# 13-EXTENSION.net
KiCad netlist of a schematic drawn in Altium Designer
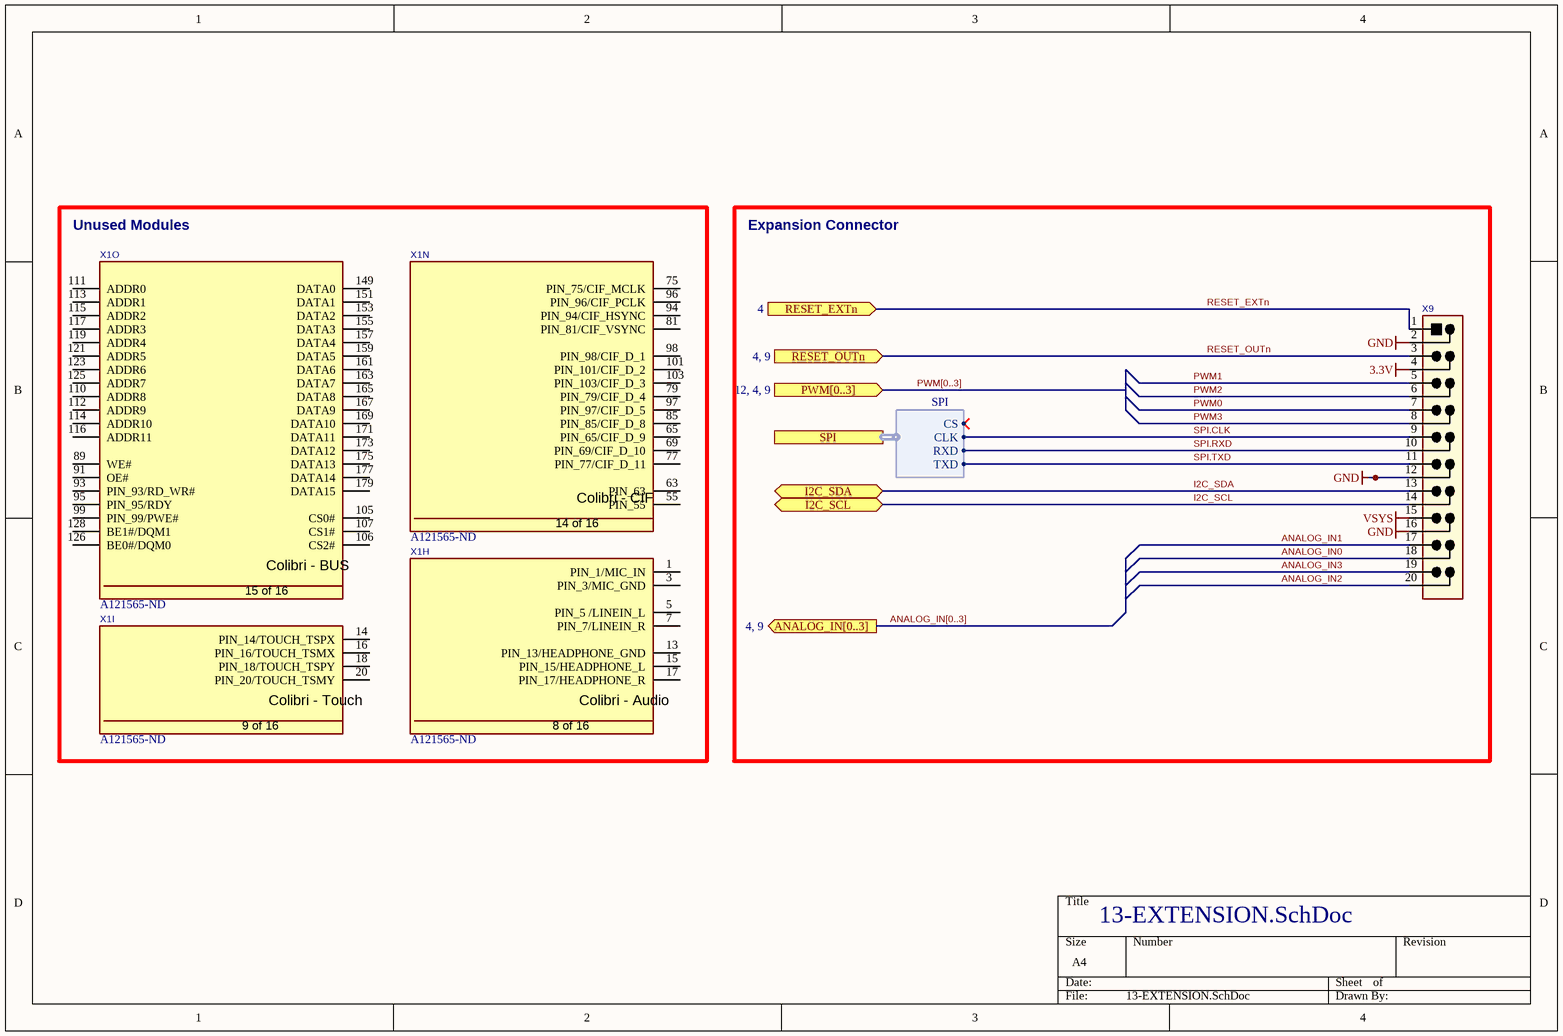
[diagram p0: 13-EXTENSION.SchDoc]

(export (version "E")
  (design (tool "Eeschema 10.0.6"))
  (components
    (comp (ref "X1")
      (value "1473005-1")
      (footprint "T_Tyco_1473005-1")
      (description "SODIMM Connector")
      (fields (field (name "SUPPLIER PART NUMBER 1") "A121565-ND"))
      (libsource (lib "Connectors") (part "CON-Tyco-1473005-1-200-0.6mm"))
    )
    (comp (ref "X9")
      (value "PH2-20-UA")
      (footprint "T_JVE_21B22564-40S10B-01G")
      (description "Connector Header Through Hole 20 position 0.100\" (2.54mm)")
      (fields (field (name "MFG") "FCI"))
      (libsource (lib "AI Gateway - Carrier") (part "CON-Adam-PH2-20-UA-2X10-2.54mm"))
    )
  )
  (nets
    (net (code "2") (name "/ANALOG_IN0") (class "Default")
      (node (ref "X9") (pin "18") (pinfunction "18_18") (pintype "passive"))
    )
    (net (code "3") (name "/ANALOG_IN1") (class "Default")
      (node (ref "X9") (pin "17") (pinfunction "17_17") (pintype "passive"))
    )
    (net (code "4") (name "/ANALOG_IN2") (class "Default")
      (node (ref "X9") (pin "20") (pinfunction "20_20") (pintype "passive"))
    )
    (net (code "5") (name "/ANALOG_IN3") (class "Default")
      (node (ref "X9") (pin "19") (pinfunction "19_19") (pintype "passive"))
    )
    (net (code "7") (name "/I2C_SCL") (class "Default")
      (node (ref "X9") (pin "14") (pinfunction "14_14") (pintype "passive"))
    )
    (net (code "8") (name "/I2C_SDA") (class "Default")
      (node (ref "X9") (pin "13") (pinfunction "13_13") (pintype "passive"))
    )
    (net (code "9") (name "/PWM0") (class "Default")
      (node (ref "X9") (pin "7") (pinfunction "7_7") (pintype "passive"))
    )
    (net (code "10") (name "/PWM1") (class "Default")
      (node (ref "X9") (pin "5") (pinfunction "5_5") (pintype "passive"))
    )
    (net (code "11") (name "/PWM2") (class "Default")
      (node (ref "X9") (pin "6") (pinfunction "6_6") (pintype "passive"))
    )
    (net (code "12") (name "/PWM3") (class "Default")
      (node (ref "X9") (pin "8") (pinfunction "8_8") (pintype "passive"))
    )
    (net (code "14") (name "/RESET_EXTn") (class "Default")
      (node (ref "X9") (pin "1") (pinfunction "1_1") (pintype "passive"))
    )
    (net (code "15") (name "/RESET_OUTn") (class "Default")
      (node (ref "X9") (pin "3") (pinfunction "3_3") (pintype "passive"))
    )
    (net (code "16") (name "/SPI.CLK") (class "Default")
      (node (ref "X9") (pin "9") (pinfunction "9_9") (pintype "passive"))
    )
    (net (code "17") (name "/SPI.RXD") (class "Default")
      (node (ref "X9") (pin "10") (pinfunction "10_10") (pintype "passive"))
    )
    (net (code "18") (name "/SPI.TXD") (class "Default")
      (node (ref "X9") (pin "11") (pinfunction "11_11") (pintype "passive"))
    )
    (net (code "20") (name "3.3V") (class "Default")
      (node (ref "X9") (pin "4") (pinfunction "4_4") (pintype "passive"))
    )
    (net (code "21") (name "GND") (class "Default")
      (node (ref "X9") (pin "12") (pinfunction "12_12") (pintype "passive"))
      (node (ref "X9") (pin "16") (pinfunction "16_16") (pintype "passive"))
      (node (ref "X9") (pin "2") (pinfunction "2_2") (pintype "passive"))
    )
    (net (code "22") (name "VSYS") (class "Default")
      (node (ref "X9") (pin "15") (pinfunction "15_15") (pintype "passive"))
    )
    (net (code "23") (name "unconnected-(X1H-PIN_1{slash}MIC_IN-Pad1)") (class "Default")
      (node (ref "X1") (pin "1") (pinfunction "PIN_1/MIC_IN_1") (pintype "passive"))
    )
    (net (code "24") (name "unconnected-(X1H-PIN_3{slash}MIC_GND-Pad3)") (class "Default")
      (node (ref "X1") (pin "3") (pinfunction "PIN_3/MIC_GND_3") (pintype "passive"))
    )
    (net (code "25") (name "unconnected-(X1H-PIN_5_{slash}LINEIN_L-Pad5)") (class "Default")
      (node (ref "X1") (pin "5") (pinfunction "PIN_5_/LINEIN_L_5") (pintype "passive"))
    )
    (net (code "26") (name "unconnected-(X1H-PIN_7{slash}LINEIN_R-Pad7)") (class "Default")
      (node (ref "X1") (pin "7") (pinfunction "PIN_7/LINEIN_R_7") (pintype "passive"))
    )
    (net (code "27") (name "unconnected-(X1H-PIN_13{slash}HEADPHONE_GND-Pad13)") (class "Default")
      (node (ref "X1") (pin "13") (pinfunction "PIN_13/HEADPHONE_GND_13") (pintype "passive"))
    )
    (net (code "28") (name "unconnected-(X1H-PIN_15{slash}HEADPHONE_L-Pad15)") (class "Default")
      (node (ref "X1") (pin "15") (pinfunction "PIN_15/HEADPHONE_L_15") (pintype "passive"))
    )
    (net (code "29") (name "unconnected-(X1H-PIN_17{slash}HEADPHONE_R-Pad17)") (class "Default")
      (node (ref "X1") (pin "17") (pinfunction "PIN_17/HEADPHONE_R_17") (pintype "passive"))
    )
    (net (code "30") (name "unconnected-(X1I-PIN_14{slash}TOUCH_TSPX-Pad14)") (class "Default")
      (node (ref "X1") (pin "14") (pinfunction "PIN_14/TOUCH_TSPX_14") (pintype "passive"))
    )
    (net (code "31") (name "unconnected-(X1I-PIN_16{slash}TOUCH_TSMX-Pad16)") (class "Default")
      (node (ref "X1") (pin "16") (pinfunction "PIN_16/TOUCH_TSMX_16") (pintype "passive"))
    )
    (net (code "32") (name "unconnected-(X1I-PIN_18{slash}TOUCH_TSPY-Pad18)") (class "Default")
      (node (ref "X1") (pin "18") (pinfunction "PIN_18/TOUCH_TSPY_18") (pintype "passive"))
    )
    (net (code "33") (name "unconnected-(X1I-PIN_20{slash}TOUCH_TSMY-Pad20)") (class "Default")
      (node (ref "X1") (pin "20") (pinfunction "PIN_20/TOUCH_TSMY_20") (pintype "passive"))
    )
    (net (code "34") (name "unconnected-(X1N-PIN_55-Pad55)") (class "Default")
      (node (ref "X1") (pin "55") (pinfunction "PIN_55_55") (pintype "passive"))
    )
    (net (code "35") (name "unconnected-(X1N-PIN_63-Pad63)") (class "Default")
      (node (ref "X1") (pin "63") (pinfunction "PIN_63_63") (pintype "passive"))
    )
    (net (code "36") (name "unconnected-(X1N-PIN_65{slash}CIF_D_9-Pad65)") (class "Default")
      (node (ref "X1") (pin "65") (pinfunction "PIN_65/CIF_D_9_65") (pintype "passive"))
    )
    (net (code "37") (name "unconnected-(X1N-PIN_69{slash}CIF_D_10-Pad69)") (class "Default")
      (node (ref "X1") (pin "69") (pinfunction "PIN_69/CIF_D_10_69") (pintype "passive"))
    )
    (net (code "38") (name "unconnected-(X1N-PIN_75{slash}CIF_MCLK-Pad75)") (class "Default")
      (node (ref "X1") (pin "75") (pinfunction "PIN_75/CIF_MCLK_75") (pintype "passive"))
    )
    (net (code "39") (name "unconnected-(X1N-PIN_77{slash}CIF_D_11-Pad77)") (class "Default")
      (node (ref "X1") (pin "77") (pinfunction "PIN_77/CIF_D_11_77") (pintype "passive"))
    )
    (net (code "40") (name "unconnected-(X1N-PIN_79{slash}CIF_D_4-Pad79)") (class "Default")
      (node (ref "X1") (pin "79") (pinfunction "PIN_79/CIF_D_4_79") (pintype "passive"))
    )
    (net (code "41") (name "unconnected-(X1N-PIN_81{slash}CIF_VSYNC-Pad81)") (class "Default")
      (node (ref "X1") (pin "81") (pinfunction "PIN_81/CIF_VSYNC_81") (pintype "passive"))
    )
    (net (code "42") (name "unconnected-(X1N-PIN_85{slash}CIF_D_8-Pad85)") (class "Default")
      (node (ref "X1") (pin "85") (pinfunction "PIN_85/CIF_D_8_85") (pintype "passive"))
    )
    (net (code "43") (name "unconnected-(X1N-PIN_94{slash}CIF_HSYNC-Pad94)") (class "Default")
      (node (ref "X1") (pin "94") (pinfunction "PIN_94/CIF_HSYNC_94") (pintype "passive"))
    )
    (net (code "44") (name "unconnected-(X1N-PIN_96{slash}CIF_PCLK-Pad96)") (class "Default")
      (node (ref "X1") (pin "96") (pinfunction "PIN_96/CIF_PCLK_96") (pintype "passive"))
    )
    (net (code "45") (name "unconnected-(X1N-PIN_97{slash}CIF_D_5-Pad97)") (class "Default")
      (node (ref "X1") (pin "97") (pinfunction "PIN_97/CIF_D_5_97") (pintype "passive"))
    )
    (net (code "46") (name "unconnected-(X1N-PIN_98{slash}CIF_D_1-Pad98)") (class "Default")
      (node (ref "X1") (pin "98") (pinfunction "PIN_98/CIF_D_1_98") (pintype "passive"))
    )
    (net (code "47") (name "unconnected-(X1N-PIN_101{slash}CIF_D_2-Pad101)") (class "Default")
      (node (ref "X1") (pin "101") (pinfunction "PIN_101/CIF_D_2_101") (pintype "passive"))
    )
    (net (code "48") (name "unconnected-(X1N-PIN_103{slash}CIF_D_3-Pad103)") (class "Default")
      (node (ref "X1") (pin "103") (pinfunction "PIN_103/CIF_D_3_103") (pintype "passive"))
    )
    (net (code "49") (name "unconnected-(X1O-ADDR0-Pad111)") (class "Default")
      (node (ref "X1") (pin "111") (pinfunction "ADDR0_111") (pintype "passive"))
    )
    (net (code "50") (name "unconnected-(X1O-ADDR1-Pad113)") (class "Default")
      (node (ref "X1") (pin "113") (pinfunction "ADDR1_113") (pintype "passive"))
    )
    (net (code "51") (name "unconnected-(X1O-ADDR2-Pad115)") (class "Default")
      (node (ref "X1") (pin "115") (pinfunction "ADDR2_115") (pintype "passive"))
    )
    (net (code "52") (name "unconnected-(X1O-ADDR3-Pad117)") (class "Default")
      (node (ref "X1") (pin "117") (pinfunction "ADDR3_117") (pintype "passive"))
    )
    (net (code "53") (name "unconnected-(X1O-ADDR4-Pad119)") (class "Default")
      (node (ref "X1") (pin "119") (pinfunction "ADDR4_119") (pintype "passive"))
    )
    (net (code "54") (name "unconnected-(X1O-ADDR5-Pad121)") (class "Default")
      (node (ref "X1") (pin "121") (pinfunction "ADDR5_121") (pintype "passive"))
    )
    (net (code "55") (name "unconnected-(X1O-ADDR6-Pad123)") (class "Default")
      (node (ref "X1") (pin "123") (pinfunction "ADDR6_123") (pintype "passive"))
    )
    (net (code "56") (name "unconnected-(X1O-ADDR7-Pad125)") (class "Default")
      (node (ref "X1") (pin "125") (pinfunction "ADDR7_125") (pintype "passive"))
    )
    (net (code "57") (name "unconnected-(X1O-ADDR8-Pad110)") (class "Default")
      (node (ref "X1") (pin "110") (pinfunction "ADDR8_110") (pintype "passive"))
    )
    (net (code "58") (name "unconnected-(X1O-ADDR9-Pad112)") (class "Default")
      (node (ref "X1") (pin "112") (pinfunction "ADDR9_112") (pintype "passive"))
    )
    (net (code "59") (name "unconnected-(X1O-ADDR10-Pad114)") (class "Default")
      (node (ref "X1") (pin "114") (pinfunction "ADDR10_114") (pintype "passive"))
    )
    (net (code "60") (name "unconnected-(X1O-ADDR11-Pad116)") (class "Default")
      (node (ref "X1") (pin "116") (pinfunction "ADDR11_116") (pintype "passive"))
    )
    (net (code "61") (name "unconnected-(X1O-BE0#{slash}DQM0-Pad126)") (class "Default")
      (node (ref "X1") (pin "126") (pinfunction "BE0#/DQM0_126") (pintype "passive"))
    )
    (net (code "62") (name "unconnected-(X1O-BE1#{slash}DQM1-Pad128)") (class "Default")
      (node (ref "X1") (pin "128") (pinfunction "BE1#/DQM1_128") (pintype "passive"))
    )
    (net (code "63") (name "unconnected-(X1O-CS0#-Pad105)") (class "Default")
      (node (ref "X1") (pin "105") (pinfunction "CS0#_105") (pintype "passive"))
    )
    (net (code "64") (name "unconnected-(X1O-CS1#-Pad107)") (class "Default")
      (node (ref "X1") (pin "107") (pinfunction "CS1#_107") (pintype "passive"))
    )
    (net (code "65") (name "unconnected-(X1O-CS2#-Pad106)") (class "Default")
      (node (ref "X1") (pin "106") (pinfunction "CS2#_106") (pintype "passive"))
    )
    (net (code "66") (name "unconnected-(X1O-DATA0-Pad149)") (class "Default")
      (node (ref "X1") (pin "149") (pinfunction "DATA0_149") (pintype "passive"))
    )
    (net (code "67") (name "unconnected-(X1O-DATA1-Pad151)") (class "Default")
      (node (ref "X1") (pin "151") (pinfunction "DATA1_151") (pintype "passive"))
    )
    (net (code "68") (name "unconnected-(X1O-DATA2-Pad153)") (class "Default")
      (node (ref "X1") (pin "153") (pinfunction "DATA2_153") (pintype "passive"))
    )
    (net (code "69") (name "unconnected-(X1O-DATA3-Pad155)") (class "Default")
      (node (ref "X1") (pin "155") (pinfunction "DATA3_155") (pintype "passive"))
    )
    (net (code "70") (name "unconnected-(X1O-DATA4-Pad157)") (class "Default")
      (node (ref "X1") (pin "157") (pinfunction "DATA4_157") (pintype "passive"))
    )
    (net (code "71") (name "unconnected-(X1O-DATA5-Pad159)") (class "Default")
      (node (ref "X1") (pin "159") (pinfunction "DATA5_159") (pintype "passive"))
    )
    (net (code "72") (name "unconnected-(X1O-DATA6-Pad161)") (class "Default")
      (node (ref "X1") (pin "161") (pinfunction "DATA6_161") (pintype "passive"))
    )
    (net (code "73") (name "unconnected-(X1O-DATA7-Pad163)") (class "Default")
      (node (ref "X1") (pin "163") (pinfunction "DATA7_163") (pintype "passive"))
    )
    (net (code "74") (name "unconnected-(X1O-DATA8-Pad165)") (class "Default")
      (node (ref "X1") (pin "165") (pinfunction "DATA8_165") (pintype "passive"))
    )
    (net (code "75") (name "unconnected-(X1O-DATA9-Pad167)") (class "Default")
      (node (ref "X1") (pin "167") (pinfunction "DATA9_167") (pintype "passive"))
    )
    (net (code "76") (name "unconnected-(X1O-DATA10-Pad169)") (class "Default")
      (node (ref "X1") (pin "169") (pinfunction "DATA10_169") (pintype "passive"))
    )
    (net (code "77") (name "unconnected-(X1O-DATA11-Pad171)") (class "Default")
      (node (ref "X1") (pin "171") (pinfunction "DATA11_171") (pintype "passive"))
    )
    (net (code "78") (name "unconnected-(X1O-DATA12-Pad173)") (class "Default")
      (node (ref "X1") (pin "173") (pinfunction "DATA12_173") (pintype "passive"))
    )
    (net (code "79") (name "unconnected-(X1O-DATA13-Pad175)") (class "Default")
      (node (ref "X1") (pin "175") (pinfunction "DATA13_175") (pintype "passive"))
    )
    (net (code "80") (name "unconnected-(X1O-DATA14-Pad177)") (class "Default")
      (node (ref "X1") (pin "177") (pinfunction "DATA14_177") (pintype "passive"))
    )
    (net (code "81") (name "unconnected-(X1O-DATA15-Pad179)") (class "Default")
      (node (ref "X1") (pin "179") (pinfunction "DATA15_179") (pintype "passive"))
    )
    (net (code "82") (name "unconnected-(X1O-OE#-Pad91)") (class "Default")
      (node (ref "X1") (pin "91") (pinfunction "OE#_91") (pintype "passive"))
    )
    (net (code "83") (name "unconnected-(X1O-PIN_93{slash}RD_WR#-Pad93)") (class "Default")
      (node (ref "X1") (pin "93") (pinfunction "PIN_93/RD_WR#_93") (pintype "passive"))
    )
    (net (code "84") (name "unconnected-(X1O-PIN_95{slash}RDY-Pad95)") (class "Default")
      (node (ref "X1") (pin "95") (pinfunction "PIN_95/RDY_95") (pintype "passive"))
    )
    (net (code "85") (name "unconnected-(X1O-PIN_99{slash}PWE#-Pad99)") (class "Default")
      (node (ref "X1") (pin "99") (pinfunction "PIN_99/PWE#_99") (pintype "passive"))
    )
    (net (code "86") (name "unconnected-(X1O-WE#-Pad89)") (class "Default")
      (node (ref "X1") (pin "89") (pinfunction "WE#_89") (pintype "passive"))
    )
  )
)
